# rapidshark-display-shifter-mk-3_2.net
KiCad netlist of a schematic drawn in EAGLE
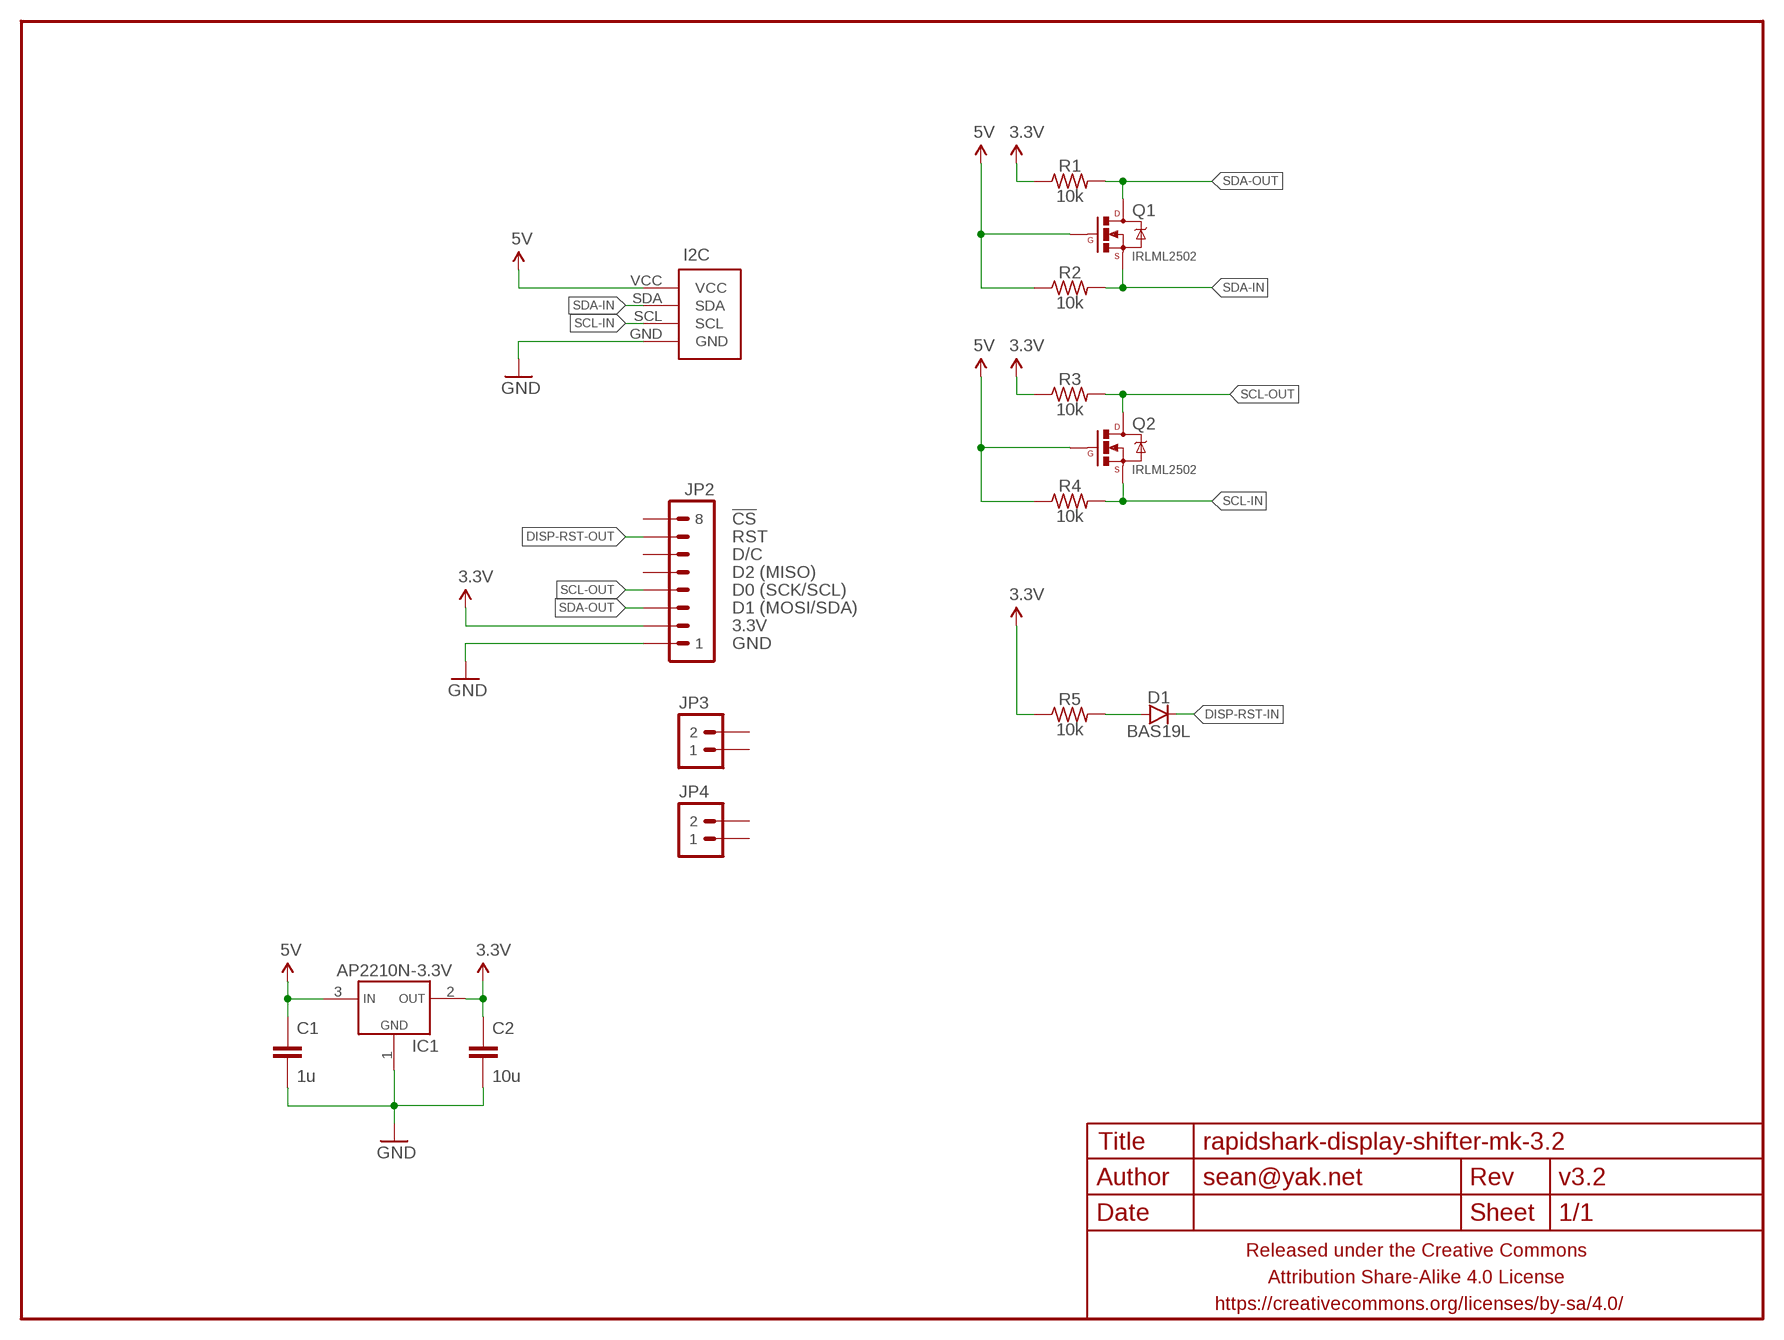
[diagram p0: schematic, sheet 1]

(export (version "E")
  (design (tool "Eeschema 10.0.6"))
  (components
    (comp (ref "C1")
      (value "1u")
      (footprint "eagle-import:C0805")
      (libsource (lib "eagle-import") (part "CAPACITOR-CERAMICC0805"))
    )
    (comp (ref "C2")
      (value "10u")
      (footprint "eagle-import:C0805")
      (libsource (lib "eagle-import") (part "CAPACITOR-CERAMICC0805"))
    )
    (comp (ref "D1")
      (value "BAS19L")
      (footprint "eagle-import:SOT23")
      (libsource (lib "eagle-import") (part "DIODESOT23"))
    )
    (comp (ref "FRAME1")
      (value "FRAME-LETTERNO_PACKAGE")
      (footprint "eagle-import:DUMMY")
      (fields (field (name "DESIGNER") "sean@yak.net") (field (name "VERSION") "v3.2"))
      (libsource (lib "eagle-import") (part "FRAME-LETTERNO_PACKAGE"))
    )
    (comp (ref "I2C")
      (value "M04-I2CPTH-0.1IN-CENTERED-FLIPPED")
      (footprint "eagle-import:1X04-PTH-VERT-I2C-CENTERED-FLIPPED")
      (libsource (lib "eagle-import") (part "M04-I2CPTH-0.1IN-CENTERED-FLIPPED"))
    )
    (comp (ref "IC1")
      (value "AP2210N-3.3V")
      (footprint "eagle-import:SOT23")
      (libsource (lib "eagle-import") (part "VREG_1117SOT-23"))
    )
    (comp (ref "JP2")
      (value "M081X08")
      (footprint "eagle-import:1X08")
      (libsource (lib "eagle-import") (part "M081X08"))
    )
    (comp (ref "JP3")
      (value "M021X02_NO_SILK")
      (footprint "eagle-import:1X02_NO_SILK")
      (libsource (lib "eagle-import") (part "M021X02_NO_SILK"))
    )
    (comp (ref "JP4")
      (value "M021X02_NO_SILK")
      (footprint "eagle-import:1X02_NO_SILK")
      (libsource (lib "eagle-import") (part "M021X02_NO_SILK"))
    )
    (comp (ref "Q1")
      (value "IRLML2502")
      (footprint "eagle-import:SOT23")
      (libsource (lib "eagle-import") (part "MOSFET-NCHANNELIRLML2502"))
    )
    (comp (ref "Q2")
      (value "IRLML2502")
      (footprint "eagle-import:SOT23")
      (libsource (lib "eagle-import") (part "MOSFET-NCHANNELIRLML2502"))
    )
    (comp (ref "R1")
      (value "10k")
      (footprint "eagle-import:R0603")
      (libsource (lib "eagle-import") (part "RESISTORR0603"))
    )
    (comp (ref "R2")
      (value "10k")
      (footprint "eagle-import:R0603")
      (libsource (lib "eagle-import") (part "RESISTORR0603"))
    )
    (comp (ref "R3")
      (value "10k")
      (footprint "eagle-import:R0603")
      (libsource (lib "eagle-import") (part "RESISTORR0603"))
    )
    (comp (ref "R4")
      (value "10k")
      (footprint "eagle-import:R0603")
      (libsource (lib "eagle-import") (part "RESISTORR0603"))
    )
    (comp (ref "R5")
      (value "10k")
      (footprint "eagle-import:R0603")
      (libsource (lib "eagle-import") (part "RESISTORR0603"))
    )
  )
  (nets
    (net (code "1") (name "3.3V") (class "Default")
      (node (ref "C2") (pin "1") (pinfunction "1_1") (pintype "passive"))
      (node (ref "IC1") (pin "2") (pinfunction "VOUT_2") (pintype "bidirectional"))
      (node (ref "JP2") (pin "2") (pinfunction "2_2") (pintype "passive"))
      (node (ref "R1") (pin "1") (pinfunction "1_1") (pintype "passive"))
      (node (ref "R3") (pin "1") (pinfunction "1_1") (pintype "passive"))
      (node (ref "R5") (pin "1") (pinfunction "1_1") (pintype "passive"))
    )
    (net (code "2") (name "5V") (class "Default")
      (node (ref "C1") (pin "1") (pinfunction "1_1") (pintype "passive"))
      (node (ref "I2C") (pin "VCC") (pinfunction "VCC_VCC") (pintype "bidirectional"))
      (node (ref "IC1") (pin "3") (pinfunction "VIN_3") (pintype "bidirectional"))
      (node (ref "Q1") (pin "1") (pinfunction "G_1") (pintype "passive"))
      (node (ref "Q2") (pin "1") (pinfunction "G_1") (pintype "passive"))
      (node (ref "R2") (pin "1") (pinfunction "1_1") (pintype "passive"))
      (node (ref "R4") (pin "1") (pinfunction "1_1") (pintype "passive"))
    )
    (net (code "3") (name "DISP-RST-IN") (class "Default")
      (node (ref "D1") (pin "3") (pinfunction "C_3") (pintype "passive"))
    )
    (net (code "4") (name "DISP-RST-OUT") (class "Default")
      (node (ref "JP2") (pin "7") (pinfunction "7_7") (pintype "passive"))
    )
    (net (code "5") (name "GND") (class "Default")
      (node (ref "C1") (pin "2") (pinfunction "2_2") (pintype "passive"))
      (node (ref "C2") (pin "2") (pinfunction "2_2") (pintype "passive"))
      (node (ref "I2C") (pin "GND") (pinfunction "GND_GND") (pintype "bidirectional"))
      (node (ref "IC1") (pin "1") (pinfunction "GND_1") (pintype "bidirectional"))
      (node (ref "JP2") (pin "1") (pinfunction "1_1") (pintype "passive"))
    )
    (net (code "6") (name "Net-(D1-A)") (class "Default")
      (node (ref "D1") (pin "1") (pinfunction "A_1") (pintype "passive"))
      (node (ref "R5") (pin "2") (pinfunction "2_2") (pintype "passive"))
    )
    (net (code "7") (name "SCL-IN") (class "Default")
      (node (ref "I2C") (pin "SCL") (pinfunction "SCL_SCL") (pintype "bidirectional"))
      (node (ref "Q2") (pin "2") (pinfunction "S_2") (pintype "passive"))
      (node (ref "R4") (pin "2") (pinfunction "2_2") (pintype "passive"))
    )
    (net (code "8") (name "SCL-OUT") (class "Default")
      (node (ref "JP2") (pin "4") (pinfunction "4_4") (pintype "passive"))
      (node (ref "Q2") (pin "3") (pinfunction "D_3") (pintype "passive"))
      (node (ref "R3") (pin "2") (pinfunction "2_2") (pintype "passive"))
    )
    (net (code "9") (name "SDA-IN") (class "Default")
      (node (ref "I2C") (pin "SDA") (pinfunction "SDA_SDA") (pintype "bidirectional"))
      (node (ref "Q1") (pin "2") (pinfunction "S_2") (pintype "passive"))
      (node (ref "R2") (pin "2") (pinfunction "2_2") (pintype "passive"))
    )
    (net (code "10") (name "SDA-OUT") (class "Default")
      (node (ref "JP2") (pin "3") (pinfunction "3_3") (pintype "passive"))
      (node (ref "Q1") (pin "3") (pinfunction "D_3") (pintype "passive"))
      (node (ref "R1") (pin "2") (pinfunction "2_2") (pintype "passive"))
    )
    (net (code "11") (name "unconnected-(JP2-Pad5)") (class "Default")
      (node (ref "JP2") (pin "5") (pinfunction "5_5") (pintype "passive"))
    )
    (net (code "12") (name "unconnected-(JP2-Pad6)") (class "Default")
      (node (ref "JP2") (pin "6") (pinfunction "6_6") (pintype "passive"))
    )
    (net (code "13") (name "unconnected-(JP2-Pad8)") (class "Default")
      (node (ref "JP2") (pin "8") (pinfunction "8_8") (pintype "passive"))
    )
    (net (code "14") (name "unconnected-(JP3-Pad1)") (class "Default")
      (node (ref "JP3") (pin "1") (pinfunction "1_1") (pintype "passive"))
    )
    (net (code "15") (name "unconnected-(JP3-Pad2)") (class "Default")
      (node (ref "JP3") (pin "2") (pinfunction "2_2") (pintype "passive"))
    )
    (net (code "16") (name "unconnected-(JP4-Pad1)") (class "Default")
      (node (ref "JP4") (pin "1") (pinfunction "1_1") (pintype "passive"))
    )
    (net (code "17") (name "unconnected-(JP4-Pad2)") (class "Default")
      (node (ref "JP4") (pin "2") (pinfunction "2_2") (pintype "passive"))
    )
  )
)
